# sound_detect.net
KiCad netlist of a schematic drawn in EAGLE
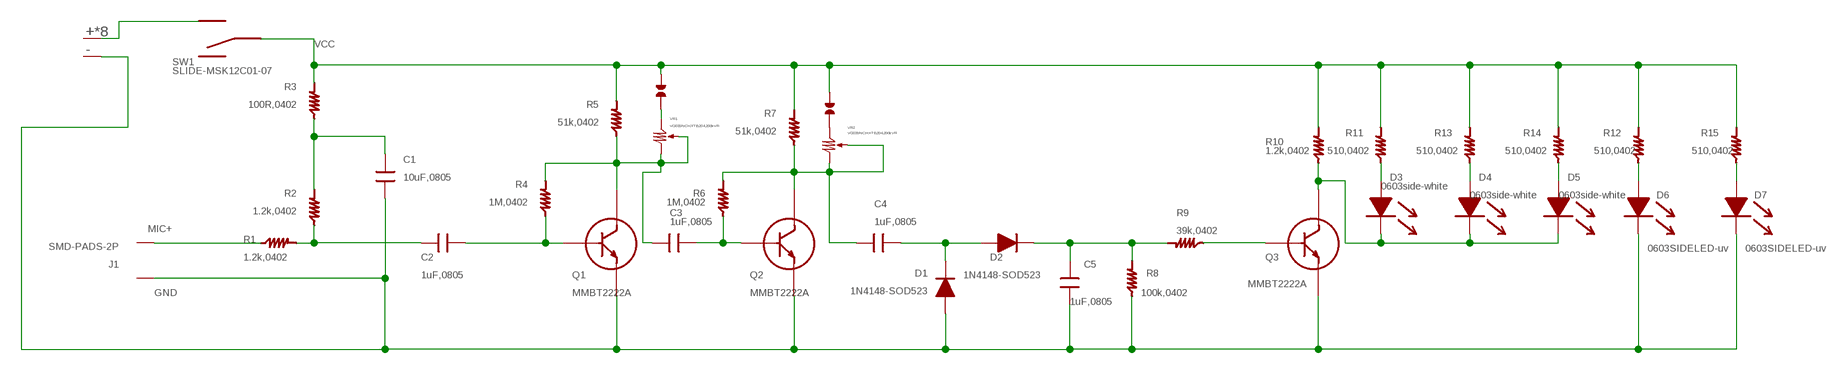
[diagram p0: schematic, sheet 1]

(export (version "E")
  (design (tool "Eeschema 10.0.6"))
  (components
    (comp (ref "C1")
      (value "10uF,0805")
      (footprint "eagle-import:CAP-0805C-LEVELB")
      (libsource (lib "eagle-import") (part "CAP-0805"))
    )
    (comp (ref "C2")
      (value "1uF,0805")
      (footprint "eagle-import:CAP-0805C-LEVELB")
      (libsource (lib "eagle-import") (part "CAP-0805"))
    )
    (comp (ref "C3")
      (value "1uF,0805")
      (footprint "eagle-import:CAP-0805C-LEVELB")
      (libsource (lib "eagle-import") (part "CAP-0805"))
    )
    (comp (ref "C4")
      (value "1uF,0805")
      (footprint "eagle-import:CAP-0805C-LEVELB")
      (libsource (lib "eagle-import") (part "CAP-0805"))
    )
    (comp (ref "C5")
      (value "1uF,0805")
      (footprint "eagle-import:CAP-0805C-LEVELB")
      (libsource (lib "eagle-import") (part "CAP-0805"))
    )
    (comp (ref "D1")
      (value "1N4148-SOD523")
      (footprint "eagle-import:SOD523")
      (libsource (lib "eagle-import") (part "1N4148-SOD523"))
    )
    (comp (ref "D2")
      (value "1N4148-SOD523")
      (footprint "eagle-import:SOD523")
      (libsource (lib "eagle-import") (part "1N4148-SOD523"))
    )
    (comp (ref "D3")
      (value "0603side-white")
      (footprint "eagle-import:SMD-0603-LED-SIDE")
      (libsource (lib "eagle-import") (part "0603SIDELED"))
    )
    (comp (ref "D4")
      (value "0603side-white")
      (footprint "eagle-import:SMD-0603-LED-SIDE")
      (libsource (lib "eagle-import") (part "0603SIDELED"))
    )
    (comp (ref "D5")
      (value "0603side-white")
      (footprint "eagle-import:SMD-0603-LED-SIDE")
      (libsource (lib "eagle-import") (part "0603SIDELED"))
    )
    (comp (ref "D6")
      (value "0603SIDELED-uv")
      (footprint "eagle-import:SMD-0603-LED-SIDE")
      (libsource (lib "eagle-import") (part "0603SIDELED"))
    )
    (comp (ref "D7")
      (value "0603SIDELED-uv")
      (footprint "eagle-import:SMD-0603-LED-SIDE")
      (libsource (lib "eagle-import") (part "0603SIDELED"))
    )
    (comp (ref "J1")
      (value "SMD-PADS-2P")
      (footprint "eagle-import:SMD-2P-2.0")
      (libsource (lib "eagle-import") (part "SMD-PADS-2P"))
    )
    (comp (ref "J2")
      (value "SHORT_PAD")
      (footprint "eagle-import:SHORTPAD")
      (libsource (lib "eagle-import") (part "SHORT_PAD"))
    )
    (comp (ref "J3")
      (value "SHORT_PAD")
      (footprint "eagle-import:SHORTPAD")
      (libsource (lib "eagle-import") (part "SHORT_PAD"))
    )
    (comp (ref "J4")
      (value "CR2032-THR")
      (footprint "eagle-import:CR2032-SMD")
      (libsource (lib "eagle-import") (part "CR2032-THR"))
    )
    (comp (ref "Q1")
      (value "MMBT2222A")
      (footprint "eagle-import:SOT23-3")
      (libsource (lib "eagle-import") (part "MMBT2222A"))
    )
    (comp (ref "Q2")
      (value "MMBT2222A")
      (footprint "eagle-import:SOT23-3")
      (libsource (lib "eagle-import") (part "MMBT2222A"))
    )
    (comp (ref "Q3")
      (value "MMBT2222A")
      (footprint "eagle-import:SOT23-3")
      (libsource (lib "eagle-import") (part "MMBT2222A"))
    )
    (comp (ref "R1")
      (value "1.2k,0402")
      (footprint "eagle-import:RES-0402R-REFLOW")
      (libsource (lib "eagle-import") (part "RES-0402"))
    )
    (comp (ref "R2")
      (value "1.2k,0402")
      (footprint "eagle-import:RES-0402R-REFLOW")
      (libsource (lib "eagle-import") (part "RES-0402"))
    )
    (comp (ref "R3")
      (value "100R,0402")
      (footprint "eagle-import:RES-0402R-REFLOW")
      (libsource (lib "eagle-import") (part "RES-0402"))
    )
    (comp (ref "R4")
      (value "1M,0402")
      (footprint "eagle-import:RES-0402R-REFLOW")
      (libsource (lib "eagle-import") (part "RES-0402"))
    )
    (comp (ref "R5")
      (value "51k,0402")
      (footprint "eagle-import:RES-0402R-REFLOW")
      (libsource (lib "eagle-import") (part "RES-0402"))
    )
    (comp (ref "R6")
      (value "1M,0402")
      (footprint "eagle-import:RES-0402R-REFLOW")
      (libsource (lib "eagle-import") (part "RES-0402"))
    )
    (comp (ref "R7")
      (value "51k,0402")
      (footprint "eagle-import:RES-0402R-REFLOW")
      (libsource (lib "eagle-import") (part "RES-0402"))
    )
    (comp (ref "R8")
      (value "100k,0402")
      (footprint "eagle-import:RES-0402R-REFLOW")
      (libsource (lib "eagle-import") (part "RES-0402"))
    )
    (comp (ref "R9")
      (value "39k,0402")
      (footprint "eagle-import:RES-0402R-REFLOW")
      (libsource (lib "eagle-import") (part "RES-0402"))
    )
    (comp (ref "R10")
      (value "1.2k,0402")
      (footprint "eagle-import:RES-0402R-REFLOW")
      (libsource (lib "eagle-import") (part "RES-0402"))
    )
    (comp (ref "R11")
      (value "510,0402")
      (footprint "eagle-import:RES-0402R-REFLOW")
      (libsource (lib "eagle-import") (part "RES-0402"))
    )
    (comp (ref "R12")
      (value "510,0402")
      (footprint "eagle-import:RES-0402R-REFLOW")
      (libsource (lib "eagle-import") (part "RES-0402"))
    )
    (comp (ref "R13")
      (value "510,0402")
      (footprint "eagle-import:RES-0402R-REFLOW")
      (libsource (lib "eagle-import") (part "RES-0402"))
    )
    (comp (ref "R14")
      (value "510,0402")
      (footprint "eagle-import:RES-0402R-REFLOW")
      (libsource (lib "eagle-import") (part "RES-0402"))
    )
    (comp (ref "R15")
      (value "510,0402")
      (footprint "eagle-import:RES-0402R-REFLOW")
      (libsource (lib "eagle-import") (part "RES-0402"))
    )
    (comp (ref "SW1")
      (value "SLIDE-MSK12C01-07")
      (footprint "eagle-import:SLIDE-SW-MSK-12C01-07")
      (libsource (lib "eagle-import") (part "SLIDE-MSK12C01-07"))
    )
    (comp (ref "VR1")
      (value "VG039NCHXTB204,200kVR")
      (footprint "eagle-import:SMD-3638")
      (libsource (lib "eagle-import") (part "VARIABLE_RES_SMD-3638"))
    )
    (comp (ref "VR2")
      (value "VG039NCHXTB204,200kVR")
      (footprint "eagle-import:SMD-3638")
      (libsource (lib "eagle-import") (part "VARIABLE_RES_SMD-3638"))
    )
  )
  (nets
    (net (code "1") (name "/GND") (class "Default")
      (node (ref "C1") (pin "P$1") (pinfunction "P$1_P$1") (pintype "bidirectional"))
      (node (ref "C5") (pin "P$2") (pinfunction "P$2_P$2") (pintype "bidirectional"))
      (node (ref "D1") (pin "A") (pinfunction "A_A") (pintype "bidirectional"))
      (node (ref "D6") (pin "C") (pinfunction "K_C") (pintype "bidirectional"))
      (node (ref "D7") (pin "C") (pinfunction "K_C") (pintype "bidirectional"))
      (node (ref "J1") (pin "P$1") (pinfunction "P$1_P$1") (pintype "bidirectional"))
      (node (ref "J4") (pin "-") (pinfunction "-_-") (pintype "bidirectional"))
      (node (ref "Q1") (pin "P$2") (pinfunction "2-E_P$2") (pintype "bidirectional"))
      (node (ref "Q2") (pin "P$2") (pinfunction "2-E_P$2") (pintype "bidirectional"))
      (node (ref "Q3") (pin "P$2") (pinfunction "2-E_P$2") (pintype "bidirectional"))
      (node (ref "R8") (pin "P$1") (pinfunction "P$1_P$1") (pintype "bidirectional"))
    )
    (net (code "2") (name "/MIC+") (class "Default")
      (node (ref "J1") (pin "P$2") (pinfunction "P$2_P$2") (pintype "bidirectional"))
      (node (ref "R1") (pin "P$1") (pinfunction "P$1_P$1") (pintype "bidirectional"))
    )
    (net (code "3") (name "/VCC") (class "Default")
      (node (ref "J2") (pin "P$2") (pinfunction "P$2_P$2") (pintype "bidirectional"))
      (node (ref "J3") (pin "P$2") (pinfunction "P$2_P$2") (pintype "bidirectional"))
      (node (ref "R10") (pin "P$2") (pinfunction "P$2_P$2") (pintype "bidirectional"))
      (node (ref "R11") (pin "P$2") (pinfunction "P$2_P$2") (pintype "bidirectional"))
      (node (ref "R12") (pin "P$2") (pinfunction "P$2_P$2") (pintype "bidirectional"))
      (node (ref "R13") (pin "P$2") (pinfunction "P$2_P$2") (pintype "bidirectional"))
      (node (ref "R14") (pin "P$2") (pinfunction "P$2_P$2") (pintype "bidirectional"))
      (node (ref "R15") (pin "P$2") (pinfunction "P$2_P$2") (pintype "bidirectional"))
      (node (ref "R3") (pin "P$2") (pinfunction "P$2_P$2") (pintype "bidirectional"))
      (node (ref "R5") (pin "P$2") (pinfunction "P$2_P$2") (pintype "bidirectional"))
      (node (ref "R7") (pin "P$2") (pinfunction "P$2_P$2") (pintype "bidirectional"))
      (node (ref "SW1") (pin "COM") (pinfunction "COM_COM") (pintype "bidirectional"))
    )
    (net (code "4") (name "Net-(C1-PadP$2)") (class "Default")
      (node (ref "C1") (pin "P$2") (pinfunction "P$2_P$2") (pintype "bidirectional"))
      (node (ref "R2") (pin "P$2") (pinfunction "P$2_P$2") (pintype "bidirectional"))
      (node (ref "R3") (pin "P$1") (pinfunction "P$1_P$1") (pintype "bidirectional"))
    )
    (net (code "5") (name "Net-(C2-PadP$2)") (class "Default")
      (node (ref "C2") (pin "P$2") (pinfunction "P$2_P$2") (pintype "bidirectional"))
      (node (ref "R1") (pin "P$2") (pinfunction "P$2_P$2") (pintype "bidirectional"))
      (node (ref "R2") (pin "P$1") (pinfunction "P$1_P$1") (pintype "bidirectional"))
    )
    (net (code "6") (name "Net-(C4-PadP$1)") (class "Default")
      (node (ref "C4") (pin "P$1") (pinfunction "P$1_P$1") (pintype "bidirectional"))
      (node (ref "D1") (pin "K") (pinfunction "K_K") (pintype "bidirectional"))
      (node (ref "D2") (pin "A") (pinfunction "A_A") (pintype "bidirectional"))
    )
    (net (code "7") (name "Net-(C5-PadP$1)") (class "Default")
      (node (ref "C5") (pin "P$1") (pinfunction "P$1_P$1") (pintype "bidirectional"))
      (node (ref "D2") (pin "K") (pinfunction "K_K") (pintype "bidirectional"))
      (node (ref "R8") (pin "P$2") (pinfunction "P$2_P$2") (pintype "bidirectional"))
      (node (ref "R9") (pin "P$2") (pinfunction "P$2_P$2") (pintype "bidirectional"))
    )
    (net (code "8") (name "Net-(D3-K)") (class "Default")
      (node (ref "D3") (pin "C") (pinfunction "K_C") (pintype "bidirectional"))
      (node (ref "D4") (pin "C") (pinfunction "K_C") (pintype "bidirectional"))
      (node (ref "D5") (pin "C") (pinfunction "K_C") (pintype "bidirectional"))
      (node (ref "Q3") (pin "P$3") (pinfunction "3-C_P$3") (pintype "bidirectional"))
      (node (ref "R10") (pin "P$1") (pinfunction "P$1_P$1") (pintype "bidirectional"))
    )
    (net (code "9") (name "Net-(D3-PadA)") (class "Default")
      (node (ref "D3") (pin "A") (pinfunction "A_A") (pintype "bidirectional"))
      (node (ref "R11") (pin "P$1") (pinfunction "P$1_P$1") (pintype "bidirectional"))
    )
    (net (code "10") (name "Net-(D4-PadA)") (class "Default")
      (node (ref "D4") (pin "A") (pinfunction "A_A") (pintype "bidirectional"))
      (node (ref "R13") (pin "P$1") (pinfunction "P$1_P$1") (pintype "bidirectional"))
    )
    (net (code "11") (name "Net-(D5-PadA)") (class "Default")
      (node (ref "D5") (pin "A") (pinfunction "A_A") (pintype "bidirectional"))
      (node (ref "R14") (pin "P$1") (pinfunction "P$1_P$1") (pintype "bidirectional"))
    )
    (net (code "12") (name "Net-(D6-PadA)") (class "Default")
      (node (ref "D6") (pin "A") (pinfunction "A_A") (pintype "bidirectional"))
      (node (ref "R12") (pin "P$1") (pinfunction "P$1_P$1") (pintype "bidirectional"))
    )
    (net (code "13") (name "Net-(D7-PadA)") (class "Default")
      (node (ref "D7") (pin "A") (pinfunction "A_A") (pintype "bidirectional"))
      (node (ref "R15") (pin "P$1") (pinfunction "P$1_P$1") (pintype "bidirectional"))
    )
    (net (code "14") (name "Net-(J2-PadP$1)") (class "Default")
      (node (ref "J2") (pin "P$1") (pinfunction "P$1_P$1") (pintype "bidirectional"))
      (node (ref "VR1") (pin "P$3") (pinfunction "P$3_P$3") (pintype "bidirectional"))
    )
    (net (code "15") (name "Net-(J3-PadP$1)") (class "Default")
      (node (ref "J3") (pin "P$1") (pinfunction "P$1_P$1") (pintype "bidirectional"))
      (node (ref "VR2") (pin "P$3") (pinfunction "P$3_P$3") (pintype "bidirectional"))
    )
    (net (code "16") (name "Net-(Q1-1-B)") (class "Default")
      (node (ref "C2") (pin "P$1") (pinfunction "P$1_P$1") (pintype "bidirectional"))
      (node (ref "Q1") (pin "P$1") (pinfunction "1-B_P$1") (pintype "bidirectional"))
      (node (ref "R4") (pin "P$1") (pinfunction "P$1_P$1") (pintype "bidirectional"))
    )
    (net (code "17") (name "Net-(Q1-3-C)") (class "Default")
      (node (ref "C3") (pin "P$2") (pinfunction "P$2_P$2") (pintype "bidirectional"))
      (node (ref "Q1") (pin "P$3") (pinfunction "3-C_P$3") (pintype "bidirectional"))
      (node (ref "R4") (pin "P$2") (pinfunction "P$2_P$2") (pintype "bidirectional"))
      (node (ref "R5") (pin "P$1") (pinfunction "P$1_P$1") (pintype "bidirectional"))
      (node (ref "VR1") (pin "P$1") (pinfunction "P$1_P$1") (pintype "bidirectional"))
      (node (ref "VR1") (pin "P$2") (pinfunction "P$2_P$2") (pintype "bidirectional"))
    )
    (net (code "18") (name "Net-(Q2-1-B)") (class "Default")
      (node (ref "C3") (pin "P$1") (pinfunction "P$1_P$1") (pintype "bidirectional"))
      (node (ref "Q2") (pin "P$1") (pinfunction "1-B_P$1") (pintype "bidirectional"))
      (node (ref "R6") (pin "P$1") (pinfunction "P$1_P$1") (pintype "bidirectional"))
    )
    (net (code "19") (name "Net-(Q2-3-C)") (class "Default")
      (node (ref "C4") (pin "P$2") (pinfunction "P$2_P$2") (pintype "bidirectional"))
      (node (ref "Q2") (pin "P$3") (pinfunction "3-C_P$3") (pintype "bidirectional"))
      (node (ref "R6") (pin "P$2") (pinfunction "P$2_P$2") (pintype "bidirectional"))
      (node (ref "R7") (pin "P$1") (pinfunction "P$1_P$1") (pintype "bidirectional"))
      (node (ref "VR2") (pin "P$1") (pinfunction "P$1_P$1") (pintype "bidirectional"))
      (node (ref "VR2") (pin "P$2") (pinfunction "P$2_P$2") (pintype "bidirectional"))
    )
    (net (code "20") (name "Net-(Q3-1-B)") (class "Default")
      (node (ref "Q3") (pin "P$1") (pinfunction "1-B_P$1") (pintype "bidirectional"))
      (node (ref "R9") (pin "P$1") (pinfunction "P$1_P$1") (pintype "bidirectional"))
    )
    (net (code "21") (name "Net-(SW1-POS-2)") (class "Default")
      (node (ref "J4") (pin "+") (pinfunction "+_+") (pintype "bidirectional"))
      (node (ref "J4") (pin "++") (pinfunction "+_++") (pintype "bidirectional"))
      (node (ref "J4") (pin "++1") (pinfunction "+_++1") (pintype "bidirectional"))
      (node (ref "J4") (pin "+1") (pinfunction "+_+1") (pintype "bidirectional"))
      (node (ref "J4") (pin "P$1") (pinfunction "+_P$1") (pintype "bidirectional"))
      (node (ref "J4") (pin "P$2") (pinfunction "+_P$2") (pintype "bidirectional"))
      (node (ref "J4") (pin "P$3") (pinfunction "+_P$3") (pintype "bidirectional"))
      (node (ref "J4") (pin "P$4") (pinfunction "+_P$4") (pintype "bidirectional"))
      (node (ref "SW1") (pin "POS2") (pinfunction "POS-2_POS2") (pintype "bidirectional"))
    )
    (net (code "22") (name "unconnected-(SW1-PadPOS1)") (class "Default")
      (node (ref "SW1") (pin "POS1") (pinfunction "POS1_POS1") (pintype "bidirectional"))
    )
  )
)
